# MUS-1099.net
KiCad netlist of a schematic drawn in EAGLE
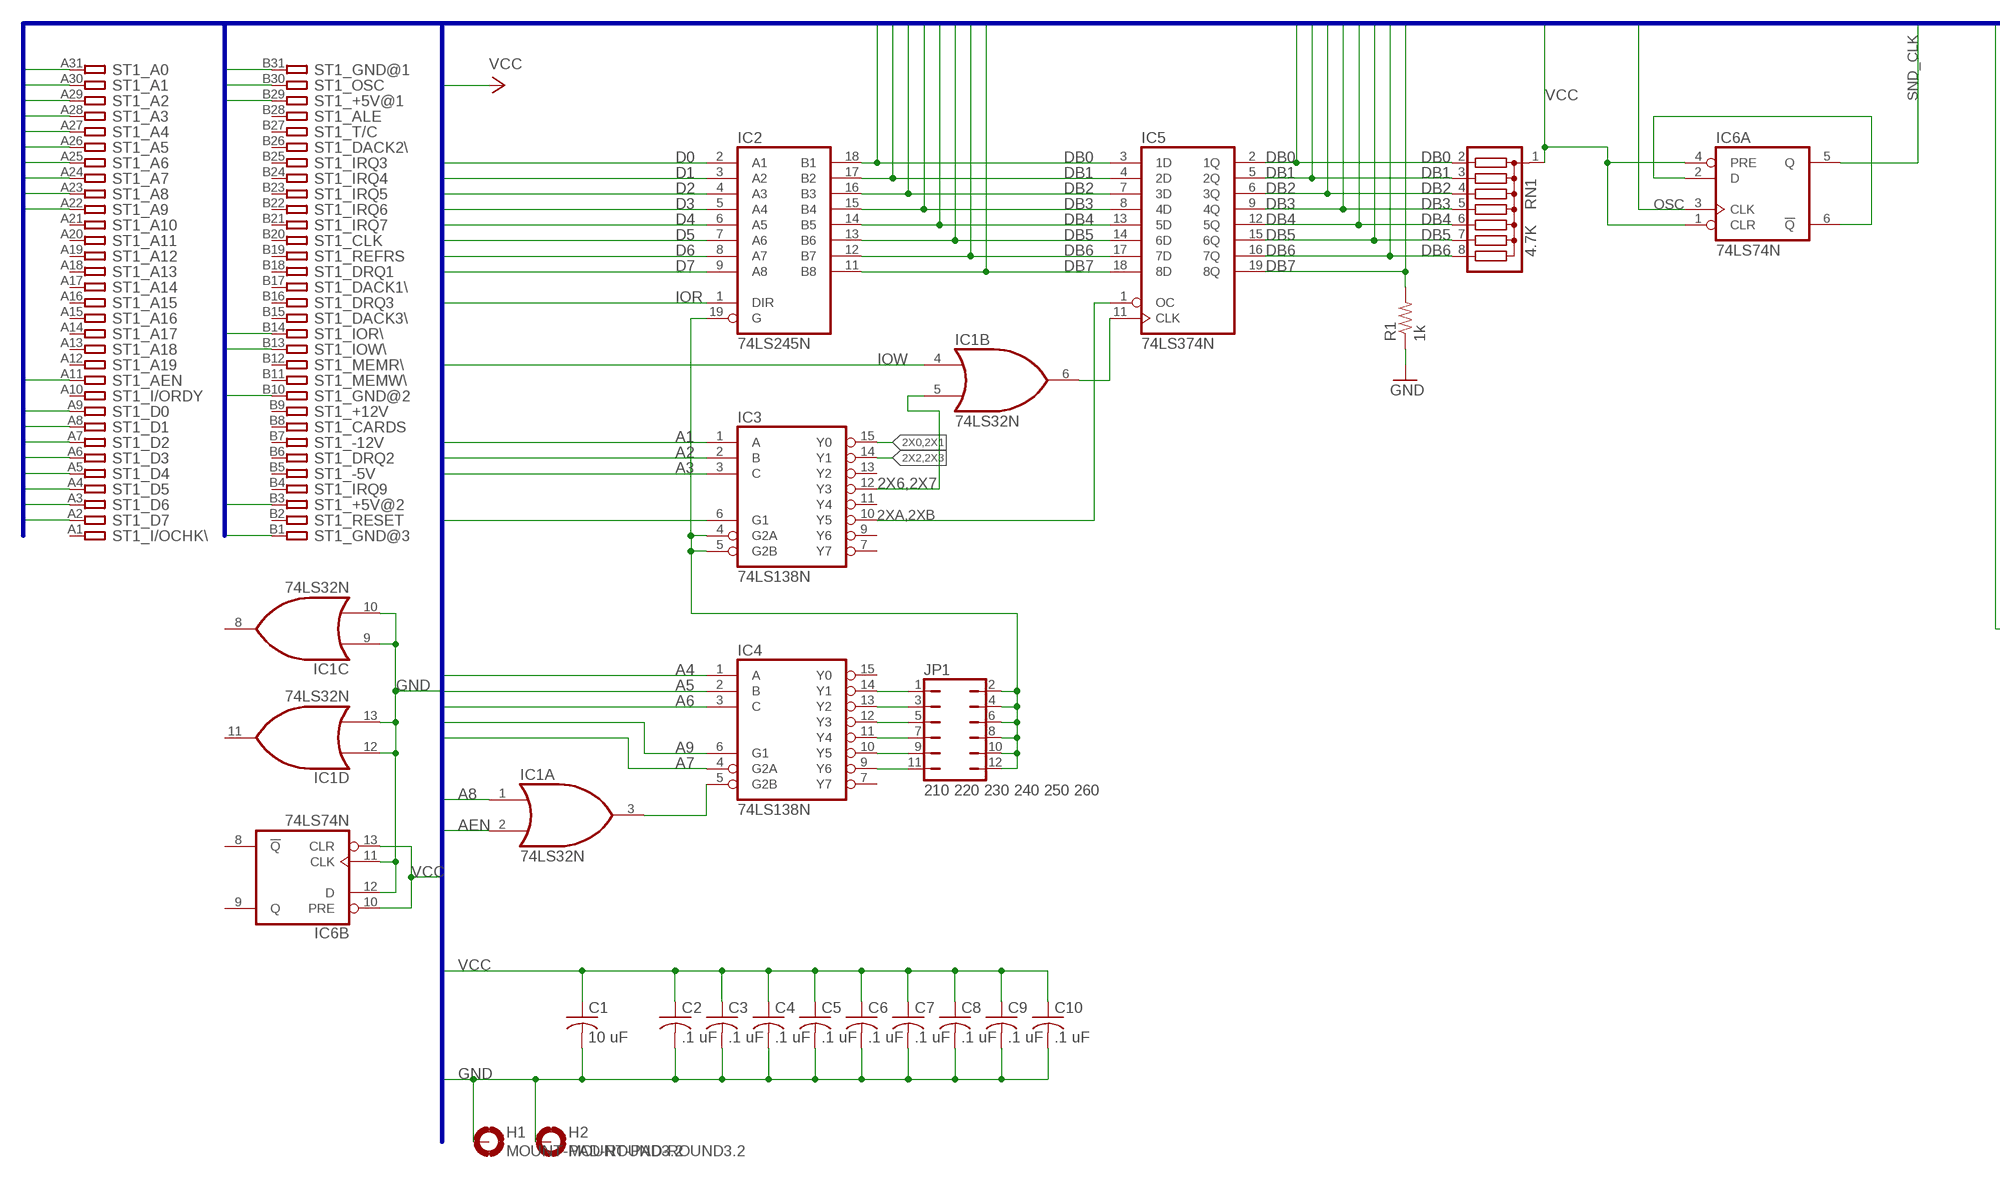
[diagram p0: schematic, sheet 1, part 1 of 2]
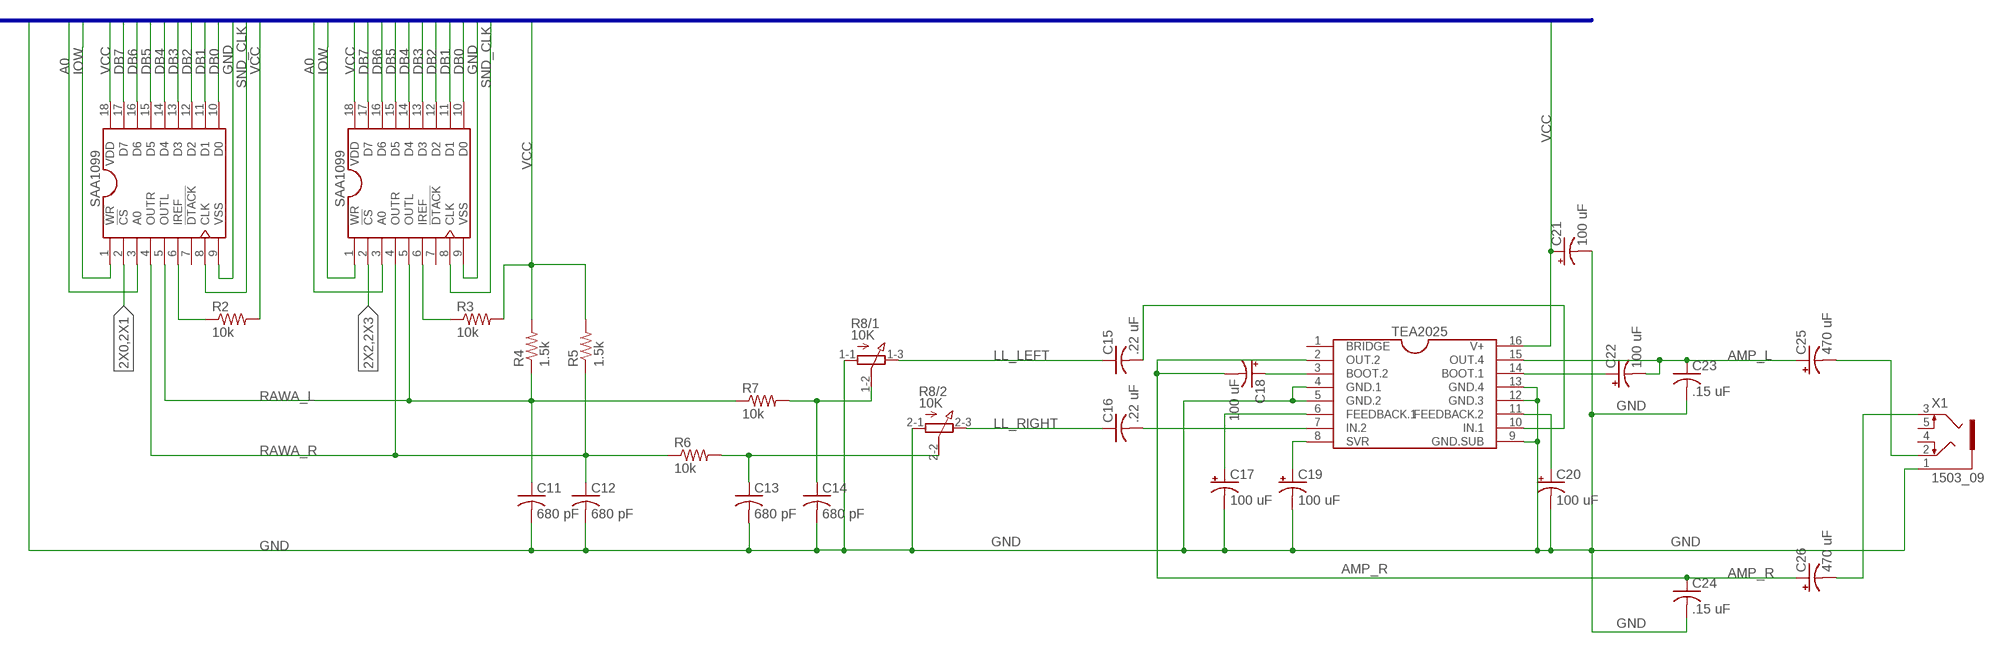
[diagram p1: schematic, sheet 1, part 2 of 2]

(export (version "E")
  (design (tool "Eeschema 10.0.6"))
  (components
    (comp (ref "C1")
      (value "10 uF")
      (footprint "eagle-import:C025-025X050")
      (libsource (lib "eagle-import") (part "C-US025-025X050"))
    )
    (comp (ref "C2")
      (value ".1 uF")
      (footprint "eagle-import:C025-025X050")
      (libsource (lib "eagle-import") (part "C-US025-025X050"))
    )
    (comp (ref "C3")
      (value ".1 uF")
      (footprint "eagle-import:C025-025X050")
      (libsource (lib "eagle-import") (part "C-US025-025X050"))
    )
    (comp (ref "C4")
      (value ".1 uF")
      (footprint "eagle-import:C025-025X050")
      (libsource (lib "eagle-import") (part "C-US025-025X050"))
    )
    (comp (ref "C5")
      (value ".1 uF")
      (footprint "eagle-import:C025-025X050")
      (libsource (lib "eagle-import") (part "C-US025-025X050"))
    )
    (comp (ref "C6")
      (value ".1 uF")
      (footprint "eagle-import:C025-025X050")
      (libsource (lib "eagle-import") (part "C-US025-025X050"))
    )
    (comp (ref "C7")
      (value ".1 uF")
      (footprint "eagle-import:C025-025X050")
      (libsource (lib "eagle-import") (part "C-US025-025X050"))
    )
    (comp (ref "C8")
      (value ".1 uF")
      (footprint "eagle-import:C025-025X050")
      (libsource (lib "eagle-import") (part "C-US025-025X050"))
    )
    (comp (ref "C9")
      (value ".1 uF")
      (footprint "eagle-import:C025-025X050")
      (libsource (lib "eagle-import") (part "C-US025-025X050"))
    )
    (comp (ref "C10")
      (value ".1 uF")
      (footprint "eagle-import:C025-025X050")
      (libsource (lib "eagle-import") (part "C-US025-025X050"))
    )
    (comp (ref "C11")
      (value "680 pF")
      (footprint "eagle-import:C025-025X050")
      (libsource (lib "eagle-import") (part "C-US025-025X050"))
    )
    (comp (ref "C12")
      (value "680 pF")
      (footprint "eagle-import:C025-025X050")
      (libsource (lib "eagle-import") (part "C-US025-025X050"))
    )
    (comp (ref "C13")
      (value "680 pF")
      (footprint "eagle-import:C025-025X050")
      (libsource (lib "eagle-import") (part "C-US025-025X050"))
    )
    (comp (ref "C14")
      (value "680 pF")
      (footprint "eagle-import:C025-025X050")
      (libsource (lib "eagle-import") (part "C-US025-025X050"))
    )
    (comp (ref "C15")
      (value ".22 uF")
      (footprint "eagle-import:C025-025X050")
      (libsource (lib "eagle-import") (part "C-US025-025X050"))
    )
    (comp (ref "C16")
      (value ".22 uF")
      (footprint "eagle-import:C025-025X050")
      (libsource (lib "eagle-import") (part "C-US025-025X050"))
    )
    (comp (ref "C17")
      (value "100 uF")
      (footprint "eagle-import:E5-10,5")
      (libsource (lib "eagle-import") (part "CPOL-USE5-10.5"))
    )
    (comp (ref "C18")
      (value "100 uF")
      (footprint "eagle-import:E5-10,5")
      (libsource (lib "eagle-import") (part "CPOL-USE5-10.5"))
    )
    (comp (ref "C19")
      (value "100 uF")
      (footprint "eagle-import:E5-10,5")
      (libsource (lib "eagle-import") (part "CPOL-USE5-10.5"))
    )
    (comp (ref "C20")
      (value "100 uF")
      (footprint "eagle-import:E5-10,5")
      (libsource (lib "eagle-import") (part "CPOL-USE5-10.5"))
    )
    (comp (ref "C21")
      (value "100 uF")
      (footprint "eagle-import:E5-10,5")
      (libsource (lib "eagle-import") (part "CPOL-USE5-10.5"))
    )
    (comp (ref "C22")
      (value "100 uF")
      (footprint "eagle-import:E5-10,5")
      (libsource (lib "eagle-import") (part "CPOL-USE5-10.5"))
    )
    (comp (ref "C23")
      (value ".15 uF")
      (footprint "eagle-import:C025-025X050")
      (libsource (lib "eagle-import") (part "C-US025-025X050"))
    )
    (comp (ref "C24")
      (value ".15 uF")
      (footprint "eagle-import:C025-025X050")
      (libsource (lib "eagle-import") (part "C-US025-025X050"))
    )
    (comp (ref "C25")
      (value "470 uF")
      (footprint "eagle-import:E5-10,5")
      (libsource (lib "eagle-import") (part "CPOL-USE5-10.5"))
    )
    (comp (ref "C26")
      (value "470 uF")
      (footprint "eagle-import:E5-10,5")
      (libsource (lib "eagle-import") (part "CPOL-USE5-10.5"))
    )
    (comp (ref "H1")
      (value "MOUNT-PAD-ROUND3.2")
      (footprint "eagle-import:3,2-PAD")
      (libsource (lib "eagle-import") (part "MOUNT-PAD-ROUND3.2"))
    )
    (comp (ref "H2")
      (value "MOUNT-PAD-ROUND3.2")
      (footprint "eagle-import:3,2-PAD")
      (libsource (lib "eagle-import") (part "MOUNT-PAD-ROUND3.2"))
    )
    (comp (ref "IC1")
      (value "74LS32N")
      (footprint "eagle-import:DIL14")
      (libsource (lib "eagle-import") (part "7432NLS"))
    )
    (comp (ref "IC2")
      (value "74LS245N")
      (footprint "eagle-import:DIL20")
      (libsource (lib "eagle-import") (part "74245NLS"))
    )
    (comp (ref "IC3")
      (value "74LS138N")
      (footprint "eagle-import:DIL16")
      (libsource (lib "eagle-import") (part "74138NLS"))
    )
    (comp (ref "IC4")
      (value "74LS138N")
      (footprint "eagle-import:DIL16")
      (libsource (lib "eagle-import") (part "74138NLS"))
    )
    (comp (ref "IC5")
      (value "74LS374N")
      (footprint "eagle-import:DIL20")
      (libsource (lib "eagle-import") (part "74374NLS"))
    )
    (comp (ref "IC6")
      (value "74LS74N")
      (footprint "eagle-import:DIL14")
      (libsource (lib "eagle-import") (part "7474NLS"))
    )
    (comp (ref "IC7")
      (value "SAA1099")
      (footprint "eagle-import:DIL18")
      (libsource (lib "eagle-import") (part "SAA1099"))
    )
    (comp (ref "IC8")
      (value "SAA1099")
      (footprint "eagle-import:DIL18")
      (libsource (lib "eagle-import") (part "SAA1099"))
    )
    (comp (ref "IC9")
      (value "TEA2025")
      (footprint "eagle-import:DIL16")
      (libsource (lib "eagle-import") (part "TEA2025"))
    )
    (comp (ref "JP1")
      (value "210 220 230 240 250 260")
      (footprint "eagle-import:JP6Q")
      (libsource (lib "eagle-import") (part "JP6Q"))
    )
    (comp (ref "R1")
      (value "1k")
      (footprint "eagle-import:0207_10")
      (libsource (lib "eagle-import") (part "R-US_0207/10"))
    )
    (comp (ref "R2")
      (value "10k")
      (footprint "eagle-import:0207_10")
      (libsource (lib "eagle-import") (part "R-US_0207/10"))
    )
    (comp (ref "R3")
      (value "10k")
      (footprint "eagle-import:0207_10")
      (libsource (lib "eagle-import") (part "R-US_0207/10"))
    )
    (comp (ref "R4")
      (value "1.5k")
      (footprint "eagle-import:0207_10")
      (libsource (lib "eagle-import") (part "R-US_0207/10"))
    )
    (comp (ref "R5")
      (value "1.5k")
      (footprint "eagle-import:0207_10")
      (libsource (lib "eagle-import") (part "R-US_0207/10"))
    )
    (comp (ref "R6")
      (value "10k")
      (footprint "eagle-import:0207_10")
      (libsource (lib "eagle-import") (part "R-US_0207/10"))
    )
    (comp (ref "R7")
      (value "10k")
      (footprint "eagle-import:0207_10")
      (libsource (lib "eagle-import") (part "R-US_0207/10"))
    )
    (comp (ref "R8")
      (value "10K")
      (footprint "eagle-import:3RP_1610G")
      (libsource (lib "eagle-import") (part "3RP/1610G"))
    )
    (comp (ref "RN1")
      (value "4.7K")
      (footprint "eagle-import:SIL8")
      (libsource (lib "eagle-import") (part "G07R"))
    )
    (comp (ref "ST1")
      (value "8 bit ISA")
      (footprint "eagle-import:IBM8BIT")
      (libsource (lib "eagle-import") (part "IBM8BIT"))
    )
    (comp (ref "X1")
      (value "1503_09")
      (footprint "eagle-import:1503_09")
      (libsource (lib "eagle-import") (part "1503_09"))
    )
  )
  (nets
    (net (code "1") (name "/2X6,2X7") (class "Default")
      (node (ref "IC1") (pin "5") (pinfunction "I1_5") (pintype "input"))
      (node (ref "IC3") (pin "12") (pinfunction "Y3_12") (pintype "output"))
    )
    (net (code "2") (name "/2XA,2XB") (class "Default")
      (node (ref "IC3") (pin "10") (pinfunction "Y5_10") (pintype "output"))
      (node (ref "IC5") (pin "1") (pinfunction "OC_1") (pintype "input"))
    )
    (net (code "3") (name "/A0") (class "Default")
      (node (ref "IC7") (pin "3") (pinfunction "A0_3") (pintype "bidirectional"))
      (node (ref "IC8") (pin "3") (pinfunction "A0_3") (pintype "bidirectional"))
      (node (ref "ST1") (pin "A31") (pinfunction "P_A31") (pintype "bidirectional"))
    )
    (net (code "4") (name "/A1") (class "Default")
      (node (ref "IC3") (pin "1") (pinfunction "A_1") (pintype "input"))
      (node (ref "ST1") (pin "A30") (pinfunction "P_A30") (pintype "bidirectional"))
    )
    (net (code "5") (name "/A2") (class "Default")
      (node (ref "IC3") (pin "2") (pinfunction "B_2") (pintype "input"))
      (node (ref "ST1") (pin "A29") (pinfunction "P_A29") (pintype "bidirectional"))
    )
    (net (code "6") (name "/A3") (class "Default")
      (node (ref "IC3") (pin "3") (pinfunction "C_3") (pintype "input"))
      (node (ref "ST1") (pin "A28") (pinfunction "P_A28") (pintype "bidirectional"))
    )
    (net (code "7") (name "/A4") (class "Default")
      (node (ref "IC4") (pin "1") (pinfunction "A_1") (pintype "input"))
      (node (ref "ST1") (pin "A27") (pinfunction "P_A27") (pintype "bidirectional"))
    )
    (net (code "8") (name "/A5") (class "Default")
      (node (ref "IC4") (pin "2") (pinfunction "B_2") (pintype "input"))
      (node (ref "ST1") (pin "A26") (pinfunction "P_A26") (pintype "bidirectional"))
    )
    (net (code "9") (name "/A6") (class "Default")
      (node (ref "IC4") (pin "3") (pinfunction "C_3") (pintype "input"))
      (node (ref "ST1") (pin "A25") (pinfunction "P_A25") (pintype "bidirectional"))
    )
    (net (code "10") (name "/A7") (class "Default")
      (node (ref "IC4") (pin "4") (pinfunction "G2A_4") (pintype "input"))
      (node (ref "ST1") (pin "A24") (pinfunction "P_A24") (pintype "bidirectional"))
    )
    (net (code "11") (name "/A8") (class "Default")
      (node (ref "IC1") (pin "1") (pinfunction "I0_1") (pintype "input"))
      (node (ref "ST1") (pin "A23") (pinfunction "P_A23") (pintype "bidirectional"))
    )
    (net (code "12") (name "/A9") (class "Default")
      (node (ref "IC4") (pin "6") (pinfunction "G1_6") (pintype "input"))
      (node (ref "ST1") (pin "A22") (pinfunction "P_A22") (pintype "bidirectional"))
    )
    (net (code "13") (name "/AEN") (class "Default")
      (node (ref "IC1") (pin "2") (pinfunction "I1_2") (pintype "input"))
      (node (ref "ST1") (pin "A11") (pinfunction "P_A11") (pintype "bidirectional"))
    )
    (net (code "14") (name "/AMP_L") (class "Default")
      (node (ref "C22") (pin "-") (pinfunction "-_-") (pintype "passive"))
      (node (ref "C23") (pin "1") (pinfunction "1_1") (pintype "passive"))
      (node (ref "C25") (pin "+") (pinfunction "+_+") (pintype "passive"))
      (node (ref "IC9") (pin "15") (pinfunction "OUT.4_15") (pintype "bidirectional"))
    )
    (net (code "15") (name "/AMP_R") (class "Default")
      (node (ref "C18") (pin "-") (pinfunction "-_-") (pintype "passive"))
      (node (ref "C24") (pin "1") (pinfunction "1_1") (pintype "passive"))
      (node (ref "C26") (pin "+") (pinfunction "+_+") (pintype "passive"))
      (node (ref "IC9") (pin "2") (pinfunction "OUT.2_2") (pintype "bidirectional"))
    )
    (net (code "16") (name "/D0") (class "Default")
      (node (ref "IC2") (pin "2") (pinfunction "A1_2") (pintype "bidirectional"))
      (node (ref "ST1") (pin "A9") (pinfunction "P_A9") (pintype "bidirectional"))
    )
    (net (code "17") (name "/D1") (class "Default")
      (node (ref "IC2") (pin "3") (pinfunction "A2_3") (pintype "bidirectional"))
      (node (ref "ST1") (pin "A8") (pinfunction "P_A8") (pintype "bidirectional"))
    )
    (net (code "18") (name "/D2") (class "Default")
      (node (ref "IC2") (pin "4") (pinfunction "A3_4") (pintype "bidirectional"))
      (node (ref "ST1") (pin "A7") (pinfunction "P_A7") (pintype "bidirectional"))
    )
    (net (code "19") (name "/D3") (class "Default")
      (node (ref "IC2") (pin "5") (pinfunction "A4_5") (pintype "bidirectional"))
      (node (ref "ST1") (pin "A6") (pinfunction "P_A6") (pintype "bidirectional"))
    )
    (net (code "20") (name "/D4") (class "Default")
      (node (ref "IC2") (pin "6") (pinfunction "A5_6") (pintype "bidirectional"))
      (node (ref "ST1") (pin "A5") (pinfunction "P_A5") (pintype "bidirectional"))
    )
    (net (code "21") (name "/D5") (class "Default")
      (node (ref "IC2") (pin "7") (pinfunction "A6_7") (pintype "bidirectional"))
      (node (ref "ST1") (pin "A4") (pinfunction "P_A4") (pintype "bidirectional"))
    )
    (net (code "22") (name "/D6") (class "Default")
      (node (ref "IC2") (pin "8") (pinfunction "A7_8") (pintype "bidirectional"))
      (node (ref "ST1") (pin "A3") (pinfunction "P_A3") (pintype "bidirectional"))
    )
    (net (code "23") (name "/D7") (class "Default")
      (node (ref "IC2") (pin "9") (pinfunction "A8_9") (pintype "bidirectional"))
      (node (ref "ST1") (pin "A2") (pinfunction "P_A2") (pintype "bidirectional"))
    )
    (net (code "24") (name "/DB0") (class "Default")
      (node (ref "IC2") (pin "18") (pinfunction "B1_18") (pintype "bidirectional"))
      (node (ref "IC5") (pin "2") (pinfunction "1Q_2") (pintype "tri_state"))
      (node (ref "IC5") (pin "3") (pinfunction "1D_3") (pintype "input"))
      (node (ref "IC7") (pin "10") (pinfunction "D0_10") (pintype "bidirectional"))
      (node (ref "IC8") (pin "10") (pinfunction "D0_10") (pintype "bidirectional"))
      (node (ref "RN1") (pin "2") (pinfunction "2_2") (pintype "passive"))
    )
    (net (code "25") (name "/DB1") (class "Default")
      (node (ref "IC2") (pin "17") (pinfunction "B2_17") (pintype "bidirectional"))
      (node (ref "IC5") (pin "4") (pinfunction "2D_4") (pintype "input"))
      (node (ref "IC5") (pin "5") (pinfunction "2Q_5") (pintype "tri_state"))
      (node (ref "IC7") (pin "11") (pinfunction "D1_11") (pintype "bidirectional"))
      (node (ref "IC8") (pin "11") (pinfunction "D1_11") (pintype "bidirectional"))
      (node (ref "RN1") (pin "3") (pinfunction "3_3") (pintype "passive"))
    )
    (net (code "26") (name "/DB2") (class "Default")
      (node (ref "IC2") (pin "16") (pinfunction "B3_16") (pintype "bidirectional"))
      (node (ref "IC5") (pin "6") (pinfunction "3Q_6") (pintype "tri_state"))
      (node (ref "IC5") (pin "7") (pinfunction "3D_7") (pintype "input"))
      (node (ref "IC7") (pin "12") (pinfunction "D2_12") (pintype "bidirectional"))
      (node (ref "IC8") (pin "12") (pinfunction "D2_12") (pintype "bidirectional"))
      (node (ref "RN1") (pin "4") (pinfunction "4_4") (pintype "passive"))
    )
    (net (code "27") (name "/DB3") (class "Default")
      (node (ref "IC2") (pin "15") (pinfunction "B4_15") (pintype "bidirectional"))
      (node (ref "IC5") (pin "8") (pinfunction "4D_8") (pintype "input"))
      (node (ref "IC5") (pin "9") (pinfunction "4Q_9") (pintype "tri_state"))
      (node (ref "IC7") (pin "13") (pinfunction "D3_13") (pintype "bidirectional"))
      (node (ref "IC8") (pin "13") (pinfunction "D3_13") (pintype "bidirectional"))
      (node (ref "RN1") (pin "5") (pinfunction "5_5") (pintype "passive"))
    )
    (net (code "28") (name "/DB4") (class "Default")
      (node (ref "IC2") (pin "14") (pinfunction "B5_14") (pintype "bidirectional"))
      (node (ref "IC5") (pin "12") (pinfunction "5Q_12") (pintype "tri_state"))
      (node (ref "IC5") (pin "13") (pinfunction "5D_13") (pintype "input"))
      (node (ref "IC7") (pin "14") (pinfunction "D4_14") (pintype "bidirectional"))
      (node (ref "IC8") (pin "14") (pinfunction "D4_14") (pintype "bidirectional"))
      (node (ref "RN1") (pin "6") (pinfunction "6_6") (pintype "passive"))
    )
    (net (code "29") (name "/DB5") (class "Default")
      (node (ref "IC2") (pin "13") (pinfunction "B6_13") (pintype "bidirectional"))
      (node (ref "IC5") (pin "14") (pinfunction "6D_14") (pintype "input"))
      (node (ref "IC5") (pin "15") (pinfunction "6Q_15") (pintype "tri_state"))
      (node (ref "IC7") (pin "15") (pinfunction "D5_15") (pintype "bidirectional"))
      (node (ref "IC8") (pin "15") (pinfunction "D5_15") (pintype "bidirectional"))
      (node (ref "RN1") (pin "7") (pinfunction "7_7") (pintype "passive"))
    )
    (net (code "30") (name "/DB6") (class "Default")
      (node (ref "IC2") (pin "12") (pinfunction "B7_12") (pintype "bidirectional"))
      (node (ref "IC5") (pin "16") (pinfunction "7Q_16") (pintype "tri_state"))
      (node (ref "IC5") (pin "17") (pinfunction "7D_17") (pintype "input"))
      (node (ref "IC7") (pin "16") (pinfunction "D6_16") (pintype "bidirectional"))
      (node (ref "IC8") (pin "16") (pinfunction "D6_16") (pintype "bidirectional"))
      (node (ref "RN1") (pin "8") (pinfunction "8_8") (pintype "passive"))
    )
    (net (code "31") (name "/DB7") (class "Default")
      (node (ref "IC2") (pin "11") (pinfunction "B8_11") (pintype "bidirectional"))
      (node (ref "IC5") (pin "18") (pinfunction "8D_18") (pintype "input"))
      (node (ref "IC5") (pin "19") (pinfunction "8Q_19") (pintype "tri_state"))
      (node (ref "IC7") (pin "17") (pinfunction "D7_17") (pintype "bidirectional"))
      (node (ref "IC8") (pin "17") (pinfunction "D7_17") (pintype "bidirectional"))
      (node (ref "R1") (pin "2") (pinfunction "2_2") (pintype "passive"))
    )
    (net (code "32") (name "/IOR") (class "Default")
      (node (ref "IC2") (pin "1") (pinfunction "DIR_1") (pintype "input"))
      (node (ref "ST1") (pin "B14") (pinfunction "P_B14") (pintype "bidirectional"))
    )
    (net (code "33") (name "/IOW") (class "Default")
      (node (ref "IC1") (pin "4") (pinfunction "I0_4") (pintype "input"))
      (node (ref "IC7") (pin "1") (pinfunction "~{WR}_1") (pintype "bidirectional"))
      (node (ref "IC8") (pin "1") (pinfunction "~{WR}_1") (pintype "bidirectional"))
      (node (ref "ST1") (pin "B13") (pinfunction "P_B13") (pintype "bidirectional"))
    )
    (net (code "34") (name "/LL_LEFT") (class "Default")
      (node (ref "C15") (pin "1") (pinfunction "1_1") (pintype "passive"))
      (node (ref "R8") (pin "1-3") (pinfunction "E_1-3") (pintype "passive"))
    )
    (net (code "35") (name "/LL_RIGHT") (class "Default")
      (node (ref "C16") (pin "1") (pinfunction "1_1") (pintype "passive"))
      (node (ref "R8") (pin "2-3") (pinfunction "E_2-3") (pintype "passive"))
    )
    (net (code "36") (name "/OSC") (class "Default")
      (node (ref "IC6") (pin "3") (pinfunction "CLK_3") (pintype "input"))
      (node (ref "ST1") (pin "B30") (pinfunction "P_B30") (pintype "bidirectional"))
    )
    (net (code "37") (name "/RAWA_L") (class "Default")
      (node (ref "C11") (pin "1") (pinfunction "1_1") (pintype "passive"))
      (node (ref "IC7") (pin "5") (pinfunction "OUTL_5") (pintype "passive"))
      (node (ref "IC8") (pin "5") (pinfunction "OUTL_5") (pintype "passive"))
      (node (ref "R4") (pin "1") (pinfunction "1_1") (pintype "passive"))
      (node (ref "R7") (pin "1") (pinfunction "1_1") (pintype "passive"))
    )
    (net (code "38") (name "/RAWA_R") (class "Default")
      (node (ref "C12") (pin "1") (pinfunction "1_1") (pintype "passive"))
      (node (ref "IC7") (pin "4") (pinfunction "OUTR_4") (pintype "passive"))
      (node (ref "IC8") (pin "4") (pinfunction "OUTR_4") (pintype "passive"))
      (node (ref "R5") (pin "1") (pinfunction "1_1") (pintype "passive"))
      (node (ref "R6") (pin "1") (pinfunction "1_1") (pintype "passive"))
    )
    (net (code "39") (name "/SND_CLK") (class "Default")
      (node (ref "IC6") (pin "5") (pinfunction "Q_5") (pintype "output"))
      (node (ref "IC7") (pin "8") (pinfunction "CLK_8") (pintype "bidirectional"))
      (node (ref "IC8") (pin "8") (pinfunction "CLK_8") (pintype "bidirectional"))
    )
    (net (code "40") (name "2X0,2X1") (class "Default")
      (node (ref "IC3") (pin "15") (pinfunction "Y0_15") (pintype "output"))
      (node (ref "IC7") (pin "2") (pinfunction "~{CS}_2") (pintype "bidirectional"))
    )
    (net (code "41") (name "2X2,2X3") (class "Default")
      (node (ref "IC3") (pin "14") (pinfunction "Y1_14") (pintype "output"))
      (node (ref "IC8") (pin "2") (pinfunction "~{CS}_2") (pintype "bidirectional"))
    )
    (net (code "42") (name "GND") (class "Default")
      (node (ref "C1") (pin "2") (pinfunction "2_2") (pintype "passive"))
      (node (ref "C10") (pin "2") (pinfunction "2_2") (pintype "passive"))
      (node (ref "C11") (pin "2") (pinfunction "2_2") (pintype "passive"))
      (node (ref "C12") (pin "2") (pinfunction "2_2") (pintype "passive"))
      (node (ref "C13") (pin "2") (pinfunction "2_2") (pintype "passive"))
      (node (ref "C14") (pin "2") (pinfunction "2_2") (pintype "passive"))
      (node (ref "C17") (pin "-") (pinfunction "-_-") (pintype "passive"))
      (node (ref "C19") (pin "-") (pinfunction "-_-") (pintype "passive"))
      (node (ref "C2") (pin "2") (pinfunction "2_2") (pintype "passive"))
      (node (ref "C20") (pin "-") (pinfunction "-_-") (pintype "passive"))
      (node (ref "C21") (pin "-") (pinfunction "-_-") (pintype "passive"))
      (node (ref "C23") (pin "2") (pinfunction "2_2") (pintype "passive"))
      (node (ref "C24") (pin "2") (pinfunction "2_2") (pintype "passive"))
      (node (ref "C3") (pin "2") (pinfunction "2_2") (pintype "passive"))
      (node (ref "C4") (pin "2") (pinfunction "2_2") (pintype "passive"))
      (node (ref "C5") (pin "2") (pinfunction "2_2") (pintype "passive"))
      (node (ref "C6") (pin "2") (pinfunction "2_2") (pintype "passive"))
      (node (ref "C7") (pin "2") (pinfunction "2_2") (pintype "passive"))
      (node (ref "C8") (pin "2") (pinfunction "2_2") (pintype "passive"))
      (node (ref "C9") (pin "2") (pinfunction "2_2") (pintype "passive"))
      (node (ref "H1") (pin "B3,2") (pinfunction "MOUNT_B3,2") (pintype "passive"))
      (node (ref "H2") (pin "B3,2") (pinfunction "MOUNT_B3,2") (pintype "passive"))
      (node (ref "IC1") (pin "10") (pinfunction "I1_10") (pintype "input"))
      (node (ref "IC1") (pin "12") (pinfunction "I0_12") (pintype "input"))
      (node (ref "IC1") (pin "13") (pinfunction "I1_13") (pintype "input"))
      (node (ref "IC1") (pin "9") (pinfunction "I0_9") (pintype "input"))
      (node (ref "IC6") (pin "11") (pinfunction "CLK_11") (pintype "input"))
      (node (ref "IC6") (pin "12") (pinfunction "D_12") (pintype "input"))
      (node (ref "IC7") (pin "9") (pinfunction "VSS_9") (pintype "bidirectional"))
      (node (ref "IC8") (pin "9") (pinfunction "VSS_9") (pintype "bidirectional"))
      (node (ref "IC9") (pin "12") (pinfunction "GND.3_12") (pintype "bidirectional"))
      (node (ref "IC9") (pin "13") (pinfunction "GND.4_13") (pintype "bidirectional"))
      (node (ref "IC9") (pin "4") (pinfunction "GND.1_4") (pintype "bidirectional"))
      (node (ref "IC9") (pin "5") (pinfunction "GND.2_5") (pintype "bidirectional"))
      (node (ref "IC9") (pin "9") (pinfunction "GND.SUB_9") (pintype "bidirectional"))
      (node (ref "R1") (pin "1") (pinfunction "1_1") (pintype "passive"))
      (node (ref "R8") (pin "1-1") (pinfunction "A_1-1") (pintype "passive"))
      (node (ref "R8") (pin "2-1") (pinfunction "A_2-1") (pintype "passive"))
      (node (ref "ST1") (pin "B1") (pinfunction "P_B1") (pintype "bidirectional"))
      (node (ref "ST1") (pin "B10") (pinfunction "P_B10") (pintype "bidirectional"))
      (node (ref "ST1") (pin "B31") (pinfunction "P_B31") (pintype "bidirectional"))
      (node (ref "X1") (pin "1") (pinfunction "1_1") (pintype "passive"))
    )
    (net (code "43") (name "Net-(C25-Pad-)") (class "Default")
      (node (ref "C25") (pin "-") (pinfunction "-_-") (pintype "passive"))
      (node (ref "X1") (pin "2") (pinfunction "2_2") (pintype "passive"))
    )
    (net (code "44") (name "Net-(C26-Pad-)") (class "Default")
      (node (ref "C26") (pin "-") (pinfunction "-_-") (pintype "passive"))
      (node (ref "X1") (pin "3") (pinfunction "3_3") (pintype "passive"))
    )
    (net (code "45") (name "Net-(IC1A-O)") (class "Default")
      (node (ref "IC1") (pin "3") (pinfunction "O_3") (pintype "output"))
      (node (ref "IC4") (pin "5") (pinfunction "G2B_5") (pintype "input"))
    )
    (net (code "46") (name "Net-(IC1B-O)") (class "Default")
      (node (ref "IC1") (pin "6") (pinfunction "O_6") (pintype "output"))
      (node (ref "IC5") (pin "11") (pinfunction "CLK_11") (pintype "input"))
    )
    (net (code "47") (name "Net-(IC2A-G)") (class "Default")
      (node (ref "IC2") (pin "19") (pinfunction "G_19") (pintype "input"))
      (node (ref "IC3") (pin "4") (pinfunction "G2A_4") (pintype "input"))
      (node (ref "IC3") (pin "5") (pinfunction "G2B_5") (pintype "input"))
      (node (ref "JP1") (pin "10") (pinfunction "10_10") (pintype "passive"))
      (node (ref "JP1") (pin "12") (pinfunction "12_12") (pintype "passive"))
      (node (ref "JP1") (pin "2") (pinfunction "2_2") (pintype "passive"))
      (node (ref "JP1") (pin "4") (pinfunction "4_4") (pintype "passive"))
      (node (ref "JP1") (pin "6") (pinfunction "6_6") (pintype "passive"))
      (node (ref "JP1") (pin "8") (pinfunction "8_8") (pintype "passive"))
    )
    (net (code "48") (name "Net-(IC4A-Y1)") (class "Default")
      (node (ref "IC4") (pin "14") (pinfunction "Y1_14") (pintype "output"))
      (node (ref "JP1") (pin "1") (pinfunction "1_1") (pintype "passive"))
    )
    (net (code "49") (name "Net-(IC4A-Y2)") (class "Default")
      (node (ref "IC4") (pin "13") (pinfunction "Y2_13") (pintype "output"))
      (node (ref "JP1") (pin "3") (pinfunction "3_3") (pintype "passive"))
    )
    (net (code "50") (name "Net-(IC4A-Y3)") (class "Default")
      (node (ref "IC4") (pin "12") (pinfunction "Y3_12") (pintype "output"))
      (node (ref "JP1") (pin "5") (pinfunction "5_5") (pintype "passive"))
    )
    (net (code "51") (name "Net-(IC4A-Y4)") (class "Default")
      (node (ref "IC4") (pin "11") (pinfunction "Y4_11") (pintype "output"))
      (node (ref "JP1") (pin "7") (pinfunction "7_7") (pintype "passive"))
    )
    (net (code "52") (name "Net-(IC4A-Y5)") (class "Default")
      (node (ref "IC4") (pin "10") (pinfunction "Y5_10") (pintype "output"))
      (node (ref "JP1") (pin "9") (pinfunction "9_9") (pintype "passive"))
    )
    (net (code "53") (name "Net-(IC4A-Y6)") (class "Default")
      (node (ref "IC4") (pin "9") (pinfunction "Y6_9") (pintype "output"))
      (node (ref "JP1") (pin "11") (pinfunction "11_11") (pintype "passive"))
    )
    (net (code "54") (name "Net-(IC6A-D)") (class "Default")
      (node (ref "IC6") (pin "2") (pinfunction "D_2") (pintype "input"))
      (node (ref "IC6") (pin "6") (pinfunction "~{Q}_6") (pintype "output"))
    )
    (net (code "55") (name "Net-(IC7-IREF)") (class "Default")
      (node (ref "IC7") (pin "6") (pinfunction "IREF_6") (pintype "bidirectional"))
      (node (ref "R2") (pin "1") (pinfunction "1_1") (pintype "passive"))
    )
    (net (code "56") (name "Net-(IC8-IREF)") (class "Default")
      (node (ref "IC8") (pin "6") (pinfunction "IREF_6") (pintype "bidirectional"))
      (node (ref "R3") (pin "1") (pinfunction "1_1") (pintype "passive"))
    )
    (net (code "57") (name "Net-(IC9-BOOT.1)") (class "Default")
      (node (ref "C22") (pin "+") (pinfunction "+_+") (pintype "passive"))
      (node (ref "IC9") (pin "14") (pinfunction "BOOT.1_14") (pintype "bidirectional"))
    )
    (net (code "58") (name "Net-(IC9-BOOT.2)") (class "Default")
      (node (ref "C18") (pin "+") (pinfunction "+_+") (pintype "passive"))
      (node (ref "IC9") (pin "3") (pinfunction "BOOT.2_3") (pintype "bidirectional"))
    )
    (net (code "59") (name "Net-(IC9-FEEDBACK.1)") (class "Default")
      (node (ref "C17") (pin "+") (pinfunction "+_+") (pintype "passive"))
      (node (ref "IC9") (pin "6") (pinfunction "FEEDBACK.1_6") (pintype "bidirectional"))
    )
    (net (code "60") (name "Net-(IC9-FEEDBACK.2)") (class "Default")
      (node (ref "C20") (pin "+") (pinfunction "+_+") (pintype "passive"))
      (node (ref "IC9") (pin "11") (pinfunction "FEEDBACK.2_11") (pintype "bidirectional"))
    )
    (net (code "61") (name "Net-(IC9-IN.1)") (class "Default")
      (node (ref "C15") (pin "2") (pinfunction "2_2") (pintype "passive"))
      (node (ref "IC9") (pin "10") (pinfunction "IN.1_10") (pintype "bidirectional"))
    )
    (net (code "62") (name "Net-(IC9-IN.2)") (class "Default")
      (node (ref "C16") (pin "2") (pinfunction "2_2") (pintype "passive"))
      (node (ref "IC9") (pin "7") (pinfunction "IN.2_7") (pintype "bidirectional"))
    )
    (net (code "63") (name "Net-(IC9-SVR)") (class "Default")
      (node (ref "C19") (pin "+") (pinfunction "+_+") (pintype "passive"))
      (node (ref "IC9") (pin "8") (pinfunction "SVR_8") (pintype "bidirectional"))
    )
    (net (code "64") (name "Net-(R8A-S)") (class "Default")
      (node (ref "C14") (pin "1") (pinfunction "1_1") (pintype "passive"))
      (node (ref "R7") (pin "2") (pinfunction "2_2") (pintype "passive"))
      (node (ref "R8") (pin "1-2") (pinfunction "S_1-2") (pintype "passive"))
    )
    (net (code "65") (name "Net-(R8B-S)") (class "Default")
      (node (ref "C13") (pin "1") (pinfunction "1_1") (pintype "passive"))
      (node (ref "R6") (pin "2") (pinfunction "2_2") (pintype "passive"))
      (node (ref "R8") (pin "2-2") (pinfunction "S_2-2") (pintype "passive"))
    )
    (net (code "66") (name "VCC") (class "Default")
      (node (ref "C1") (pin "1") (pinfunction "1_1") (pintype "passive"))
      (node (ref "C10") (pin "1") (pinfunction "1_1") (pintype "passive"))
      (node (ref "C2") (pin "1") (pinfunction "1_1") (pintype "passive"))
      (node (ref "C21") (pin "+") (pinfunction "+_+") (pintype "passive"))
      (node (ref "C3") (pin "1") (pinfunction "1_1") (pintype "passive"))
      (node (ref "C4") (pin "1") (pinfunction "1_1") (pintype "passive"))
      (node (ref "C5") (pin "1") (pinfunction "1_1") (pintype "passive"))
      (node (ref "C6") (pin "1") (pinfunction "1_1") (pintype "passive"))
      (node (ref "C7") (pin "1") (pinfunction "1_1") (pintype "passive"))
      (node (ref "C8") (pin "1") (pinfunction "1_1") (pintype "passive"))
      (node (ref "C9") (pin "1") (pinfunction "1_1") (pintype "passive"))
      (node (ref "IC3") (pin "6") (pinfunction "G1_6") (pintype "input"))
      (node (ref "IC6") (pin "1") (pinfunction "CLR_1") (pintype "input"))
      (node (ref "IC6") (pin "10") (pinfunction "PRE_10") (pintype "input"))
      (node (ref "IC6") (pin "13") (pinfunction "CLR_13") (pintype "input"))
      (node (ref "IC6") (pin "4") (pinfunction "PRE_4") (pintype "input"))
      (node (ref "IC7") (pin "18") (pinfunction "VDD_18") (pintype "bidirectional"))
      (node (ref "IC8") (pin "18") (pinfunction "VDD_18") (pintype "bidirectional"))
      (node (ref "IC9") (pin "16") (pinfunction "V+_16") (pintype "bidirectional"))
      (node (ref "R2") (pin "2") (pinfunction "2_2") (pintype "passive"))
      (node (ref "R3") (pin "2") (pinfunction "2_2") (pintype "passive"))
      (node (ref "R4") (pin "2") (pinfunction "2_2") (pintype "passive"))
      (node (ref "R5") (pin "2") (pinfunction "2_2") (pintype "passive"))
      (node (ref "RN1") (pin "1") (pinfunction "1_1") (pintype "passive"))
      (node (ref "ST1") (pin "B29") (pinfunction "P_B29") (pintype "bidirectional"))
      (node (ref "ST1") (pin "B3") (pinfunction "P_B3") (pintype "bidirectional"))
    )
    (net (code "67") (name "unconnected-(IC1C-O-Pad8)") (class "Default")
      (node (ref "IC1") (pin "8") (pinfunction "O_8") (pintype "output"))
    )
    (net (code "68") (name "unconnected-(IC1D-O-Pad11)") (class "Default")
      (node (ref "IC1") (pin "11") (pinfunction "O_11") (pintype "output"))
    )
    (net (code "69") (name "unconnected-(IC3A-Y2-Pad13)") (class "Default")
      (node (ref "IC3") (pin "13") (pinfunction "Y2_13") (pintype "output"))
    )
    (net (code "70") (name "unconnected-(IC3A-Y4-Pad11)") (class "Default")
      (node (ref "IC3") (pin "11") (pinfunction "Y4_11") (pintype "output"))
    )
    (net (code "71") (name "unconnected-(IC3A-Y6-Pad9)") (class "Default")
      (node (ref "IC3") (pin "9") (pinfunction "Y6_9") (pintype "output"))
    )
    (net (code "72") (name "unconnected-(IC3A-Y7-Pad7)") (class "Default")
      (node (ref "IC3") (pin "7") (pinfunction "Y7_7") (pintype "output"))
    )
    (net (code "73") (name "unconnected-(IC4A-Y0-Pad15)") (class "Default")
      (node (ref "IC4") (pin "15") (pinfunction "Y0_15") (pintype "output"))
    )
    (net (code "74") (name "unconnected-(IC4A-Y7-Pad7)") (class "Default")
      (node (ref "IC4") (pin "7") (pinfunction "Y7_7") (pintype "output"))
    )
    (net (code "75") (name "unconnected-(IC6B-Q-Pad9)") (class "Default")
      (node (ref "IC6") (pin "9") (pinfunction "Q_9") (pintype "output"))
    )
    (net (code "76") (name "unconnected-(IC6B-~{Q}-Pad8)") (class "Default")
      (node (ref "IC6") (pin "8") (pinfunction "~{Q}_8") (pintype "output"))
    )
    (net (code "77") (name "unconnected-(IC7-~{DTACK}-Pad7)") (class "Default")
      (node (ref "IC7") (pin "7") (pinfunction "~{DTACK}_7") (pintype "bidirectional"))
    )
    (net (code "78") (name "unconnected-(IC8-~{DTACK}-Pad7)") (class "Default")
      (node (ref "IC8") (pin "7") (pinfunction "~{DTACK}_7") (pintype "bidirectional"))
    )
    (net (code "79") (name "unconnected-(IC9-BRIDGE-Pad1)") (class "Default")
      (node (ref "IC9") (pin "1") (pinfunction "BRIDGE_1") (pintype "bidirectional"))
    )
    (net (code "80") (name "unconnected-(ST1A-P-PadB9)") (class "Default")
      (node (ref "ST1") (pin "B9") (pinfunction "P_B9") (pintype "bidirectional"))
    )
    (net (code "81") (name "unconnected-(ST1AA-P-PadB28)") (class "Default")
      (node (ref "ST1") (pin "B28") (pinfunction "P_B28") (pintype "bidirectional"))
    )
    (net (code "82") (name "unconnected-(ST1AB-P-PadB8)") (class "Default")
      (node (ref "ST1") (pin "B8") (pinfunction "P_B8") (pintype "bidirectional"))
    )
    (net (code "83") (name "unconnected-(ST1AC-P-PadB20)") (class "Default")
      (node (ref "ST1") (pin "B20") (pinfunction "P_B20") (pintype "bidirectional"))
    )
    (net (code "84") (name "unconnected-(ST1AL-P-PadB17)") (class "Default")
      (node (ref "ST1") (pin "B17") (pinfunction "P_B17") (pintype "bidirectional"))
    )
    (net (code "85") (name "unconnected-(ST1AM-P-PadB26)") (class "Default")
      (node (ref "ST1") (pin "B26") (pinfunction "P_B26") (pintype "bidirectional"))
    )
    (net (code "86") (name "unconnected-(ST1AN-P-PadB15)") (class "Default")
      (node (ref "ST1") (pin "B15") (pinfunction "P_B15") (pintype "bidirectional"))
    )
    (net (code "87") (name "unconnected-(ST1AO-P-PadB18)") (class "Default")
      (node (ref "ST1") (pin "B18") (pinfunction "P_B18") (pintype "bidirectional"))
    )
    (net (code "88") (name "unconnected-(ST1AP-P-PadB6)") (class "Default")
      (node (ref "ST1") (pin "B6") (pinfunction "P_B6") (pintype "bidirectional"))
    )
    (net (code "89") (name "unconnected-(ST1AQ-P-PadB16)") (class "Default")
      (node (ref "ST1") (pin "B16") (pinfunction "P_B16") (pintype "bidirectional"))
    )
    (net (code "90") (name "unconnected-(ST1AU-P-PadA1)") (class "Default")
      (node (ref "ST1") (pin "A1") (pinfunction "P_A1") (pintype "bidirectional"))
    )
    (net (code "91") (name "unconnected-(ST1AV-P-PadA10)") (class "Default")
      (node (ref "ST1") (pin "A10") (pinfunction "P_A10") (pintype "bidirectional"))
    )
    (net (code "92") (name "unconnected-(ST1AY-P-PadB25)") (class "Default")
      (node (ref "ST1") (pin "B25") (pinfunction "P_B25") (pintype "bidirectional"))
    )
    (net (code "93") (name "unconnected-(ST1AZ-P-PadB24)") (class "Default")
      (node (ref "ST1") (pin "B24") (pinfunction "P_B24") (pintype "bidirectional"))
    )
    (net (code "94") (name "unconnected-(ST1BA-P-PadB23)") (class "Default")
      (node (ref "ST1") (pin "B23") (pinfunction "P_B23") (pintype "bidirectional"))
    )
    (net (code "95") (name "unconnected-(ST1BB-P-PadB22)") (class "Default")
      (node (ref "ST1") (pin "B22") (pinfunction "P_B22") (pintype "bidirectional"))
    )
    (net (code "96") (name "unconnected-(ST1BC-P-PadB21)") (class "Default")
      (node (ref "ST1") (pin "B21") (pinfunction "P_B21") (pintype "bidirectional"))
    )
    (net (code "97") (name "unconnected-(ST1BD-P-PadB4)") (class "Default")
      (node (ref "ST1") (pin "B4") (pinfunction "P_B4") (pintype "bidirectional"))
    )
    (net (code "98") (name "unconnected-(ST1BE-P-PadB12)") (class "Default")
      (node (ref "ST1") (pin "B12") (pinfunction "P_B12") (pintype "bidirectional"))
    )
    (net (code "99") (name "unconnected-(ST1BF-P-PadB11)") (class "Default")
      (node (ref "ST1") (pin "B11") (pinfunction "P_B11") (pintype "bidirectional"))
    )
    (net (code "100") (name "unconnected-(ST1BH-P-PadB19)") (class "Default")
      (node (ref "ST1") (pin "B19") (pinfunction "P_B19") (pintype "bidirectional"))
    )
    (net (code "101") (name "unconnected-(ST1BI-P-PadB2)") (class "Default")
      (node (ref "ST1") (pin "B2") (pinfunction "P_B2") (pintype "bidirectional"))
    )
    (net (code "102") (name "unconnected-(ST1BJ-P-PadB27)") (class "Default")
      (node (ref "ST1") (pin "B27") (pinfunction "P_B27") (pintype "bidirectional"))
    )
    (net (code "103") (name "unconnected-(ST1D-P-PadB7)") (class "Default")
      (node (ref "ST1") (pin "B7") (pinfunction "P_B7") (pintype "bidirectional"))
    )
    (net (code "104") (name "unconnected-(ST1E-P-PadB5)") (class "Default")
      (node (ref "ST1") (pin "B5") (pinfunction "P_B5") (pintype "bidirectional"))
    )
    (net (code "105") (name "unconnected-(ST1H-P-PadA21)") (class "Default")
      (node (ref "ST1") (pin "A21") (pinfunction "P_A21") (pintype "bidirectional"))
    )
    (net (code "106") (name "unconnected-(ST1I-P-PadA20)") (class "Default")
      (node (ref "ST1") (pin "A20") (pinfunction "P_A20") (pintype "bidirectional"))
    )
    (net (code "107") (name "unconnected-(ST1J-P-PadA19)") (class "Default")
      (node (ref "ST1") (pin "A19") (pinfunction "P_A19") (pintype "bidirectional"))
    )
    (net (code "108") (name "unconnected-(ST1K-P-PadA18)") (class "Default")
      (node (ref "ST1") (pin "A18") (pinfunction "P_A18") (pintype "bidirectional"))
    )
    (net (code "109") (name "unconnected-(ST1L-P-PadA17)") (class "Default")
      (node (ref "ST1") (pin "A17") (pinfunction "P_A17") (pintype "bidirectional"))
    )
    (net (code "110") (name "unconnected-(ST1M-P-PadA16)") (class "Default")
      (node (ref "ST1") (pin "A16") (pinfunction "P_A16") (pintype "bidirectional"))
    )
    (net (code "111") (name "unconnected-(ST1N-P-PadA15)") (class "Default")
      (node (ref "ST1") (pin "A15") (pinfunction "P_A15") (pintype "bidirectional"))
    )
    (net (code "112") (name "unconnected-(ST1O-P-PadA14)") (class "Default")
      (node (ref "ST1") (pin "A14") (pinfunction "P_A14") (pintype "bidirectional"))
    )
    (net (code "113") (name "unconnected-(ST1P-P-PadA13)") (class "Default")
      (node (ref "ST1") (pin "A13") (pinfunction "P_A13") (pintype "bidirectional"))
    )
    (net (code "114") (name "unconnected-(ST1Q-P-PadA12)") (class "Default")
      (node (ref "ST1") (pin "A12") (pinfunction "P_A12") (pintype "bidirectional"))
    )
    (net (code "115") (name "unconnected-(X1-Pad4)") (class "Default")
      (node (ref "X1") (pin "4") (pinfunction "4_4") (pintype "passive"))
    )
    (net (code "116") (name "unconnected-(X1-Pad5)") (class "Default")
      (node (ref "X1") (pin "5") (pinfunction "5_5") (pintype "passive"))
    )
  )
)
